# HAL_3.net
KiCad netlist of a schematic drawn in Altium Designer
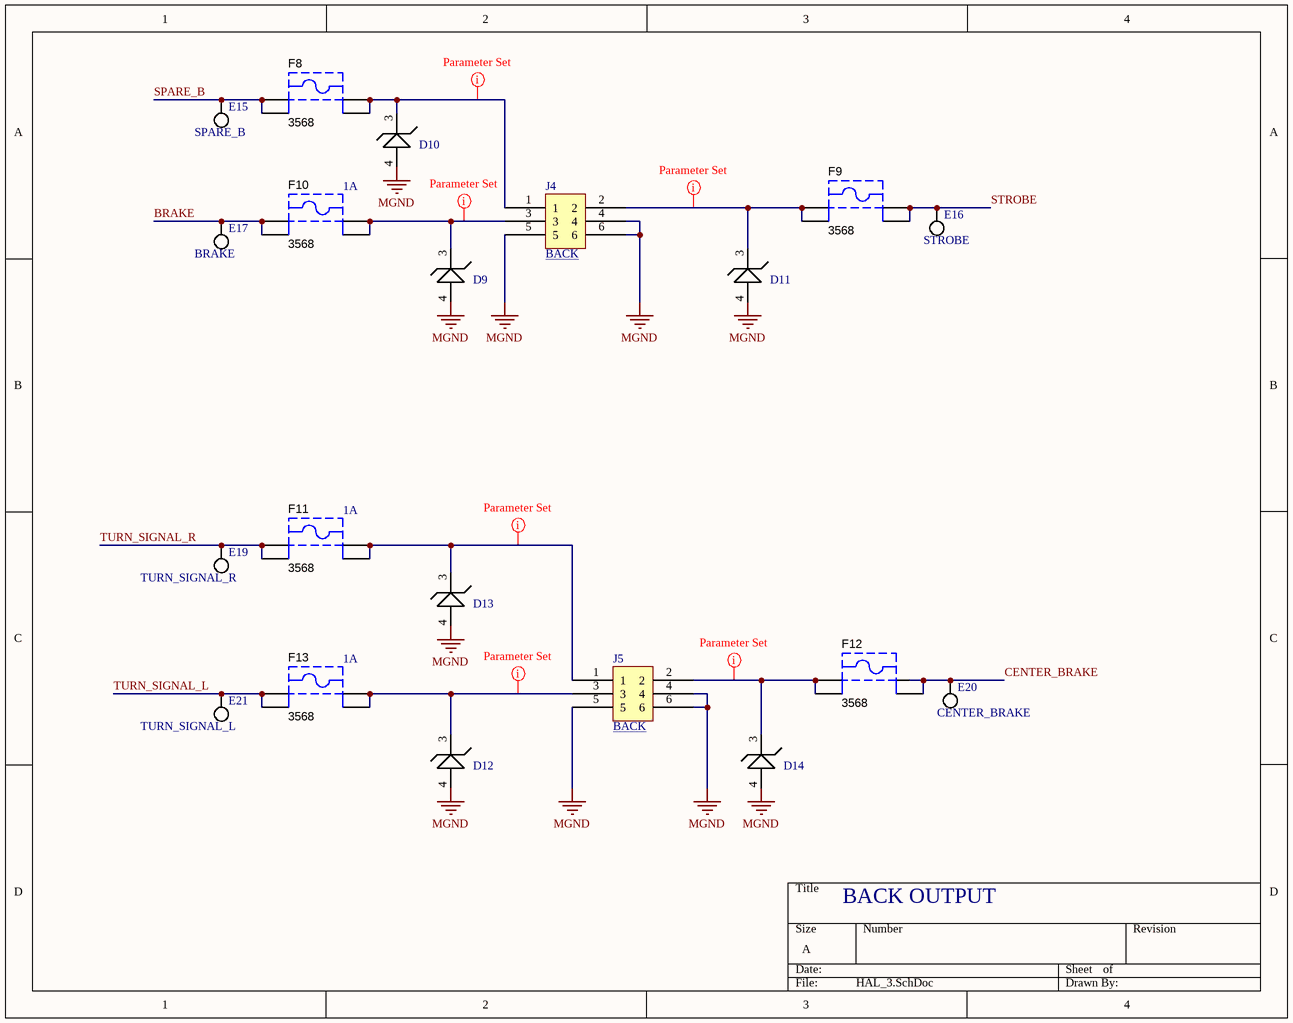
[diagram p0: HAL_3.SchDoc]

(export (version "E")
  (design (tool "Eeschema 10.0.6"))
  (components
    (comp (ref "D9")
      (value "TVS DIODE 12.4V 20.1V DO219AB")
      (footprint "TVS DIODE 12.4V 20.1V DO219AB")
      (libsource (lib "HAL and MotorBoard") (part "TVS DIODE 12.4V 20.1V DO219AB"))
    )
    (comp (ref "D10")
      (value "TVS DIODE 12.4V 20.1V DO219AB")
      (footprint "TVS DIODE 12.4V 20.1V DO219AB")
      (libsource (lib "HAL and MotorBoard") (part "TVS DIODE 12.4V 20.1V DO219AB"))
    )
    (comp (ref "D11")
      (value "TVS DIODE 12.4V 20.1V DO219AB")
      (footprint "TVS DIODE 12.4V 20.1V DO219AB")
      (libsource (lib "HAL and MotorBoard") (part "TVS DIODE 12.4V 20.1V DO219AB"))
    )
    (comp (ref "D12")
      (value "TVS DIODE 12.4V 20.1V DO219AB")
      (footprint "TVS DIODE 12.4V 20.1V DO219AB")
      (libsource (lib "HAL and MotorBoard") (part "TVS DIODE 12.4V 20.1V DO219AB"))
    )
    (comp (ref "D13")
      (value "TVS DIODE 12.4V 20.1V DO219AB")
      (footprint "TVS DIODE 12.4V 20.1V DO219AB")
      (libsource (lib "HAL and MotorBoard") (part "TVS DIODE 12.4V 20.1V DO219AB"))
    )
    (comp (ref "D14")
      (value "TVS DIODE 12.4V 20.1V DO219AB")
      (footprint "TVS DIODE 12.4V 20.1V DO219AB")
      (libsource (lib "HAL and MotorBoard") (part "TVS DIODE 12.4V 20.1V DO219AB"))
    )
    (comp (ref "E15")
      (value "SPARE_B")
      (footprint "EPAD")
      (description "Pad for probing signals")
      (libsource (lib "PrISUm-Discrete") (part "EPAD"))
    )
    (comp (ref "E16")
      (value "STROBE")
      (footprint "EPAD")
      (description "Pad for probing signals")
      (libsource (lib "PrISUm-Discrete") (part "EPAD"))
    )
    (comp (ref "E17")
      (value "BRAKE")
      (footprint "EPAD")
      (description "Pad for probing signals")
      (libsource (lib "PrISUm-Discrete") (part "EPAD"))
    )
    (comp (ref "E19")
      (value "TURN_SIGNAL_R")
      (footprint "EPAD")
      (description "Pad for probing signals")
      (libsource (lib "PrISUm-Discrete") (part "EPAD"))
    )
    (comp (ref "E20")
      (value "CENTER_BRAKE")
      (footprint "EPAD")
      (description "Pad for probing signals")
      (libsource (lib "PrISUm-Discrete") (part "EPAD"))
    )
    (comp (ref "E21")
      (value "TURN_SIGNAL_L")
      (footprint "EPAD")
      (description "Pad for probing signals")
      (libsource (lib "PrISUm-Discrete") (part "EPAD"))
    )
    (comp (ref "F8")
      (value "3568")
      (footprint "KSTN-3568_V")
      (description "Fuse Holder, 20 A, 500 V, -50 to 145 degC, 4-Pin THD, RoHS")
      (fields (field (name "MANUFACTURER") "Keystone"))
      (libsource (lib "Altium Content Vault") (part "FUSE_HOLDER-4"))
    )
    (comp (ref "F9")
      (value "3568")
      (footprint "KSTN-3568_V")
      (description "Fuse Holder, 20 A, 500 V, -50 to 145 degC, 4-Pin THD, RoHS")
      (fields (field (name "MANUFACTURER") "Keystone"))
      (libsource (lib "Altium Content Vault") (part "FUSE_HOLDER-4"))
    )
    (comp (ref "F10")
      (value "3568")
      (footprint "KSTN-3568_V")
      (description "Fuse Holder, 20 A, 500 V, -50 to 145 degC, 4-Pin THD, RoHS")
      (fields (field (name "MANUFACTURER") "Keystone"))
      (libsource (lib "Altium Content Vault") (part "FUSE_HOLDER-4"))
    )
    (comp (ref "F11")
      (value "3568")
      (footprint "KSTN-3568_V")
      (description "Fuse Holder, 20 A, 500 V, -50 to 145 degC, 4-Pin THD, RoHS")
      (fields (field (name "MANUFACTURER") "Keystone"))
      (libsource (lib "Altium Content Vault") (part "FUSE_HOLDER-4"))
    )
    (comp (ref "F12")
      (value "3568")
      (footprint "KSTN-3568_V")
      (description "Fuse Holder, 20 A, 500 V, -50 to 145 degC, 4-Pin THD, RoHS")
      (fields (field (name "MANUFACTURER") "Keystone"))
      (libsource (lib "Altium Content Vault") (part "FUSE_HOLDER-4"))
    )
    (comp (ref "F13")
      (value "3568")
      (footprint "KSTN-3568_V")
      (description "Fuse Holder, 20 A, 500 V, -50 to 145 degC, 4-Pin THD, RoHS")
      (fields (field (name "MANUFACTURER") "Keystone"))
      (libsource (lib "Altium Content Vault") (part "FUSE_HOLDER-4"))
    )
    (comp (ref "J4")
      (value "BACK")
      (footprint "PCBComponent_1 - duplicate")
      (libsource (lib "HAL") (part "6 pin Megafit"))
    )
    (comp (ref "J5")
      (value "BACK")
      (footprint "PCBComponent_1 - duplicate")
      (libsource (lib "HAL") (part "6 pin Megafit"))
    )
  )
  (nets
    (net (code "1") (name "/BRAKE") (class "Default")
      (node (ref "E17") (pin "1") (pinfunction "1_1") (pintype "passive"))
      (node (ref "F10") (pin "1") (pinfunction "1_1") (pintype "passive"))
      (node (ref "F10") (pin "2") (pinfunction "2_2") (pintype "passive"))
    )
    (net (code "2") (name "/CENTER_BRAKE") (class "Default")
      (node (ref "E20") (pin "1") (pinfunction "1_1") (pintype "passive"))
      (node (ref "F12") (pin "3") (pinfunction "3_3") (pintype "passive"))
      (node (ref "F12") (pin "4") (pinfunction "4_4") (pintype "passive"))
    )
    (net (code "3") (name "/SPARE_B") (class "Default")
      (node (ref "E15") (pin "1") (pinfunction "1_1") (pintype "passive"))
      (node (ref "F8") (pin "1") (pinfunction "1_1") (pintype "passive"))
      (node (ref "F8") (pin "2") (pinfunction "2_2") (pintype "passive"))
    )
    (net (code "4") (name "/STROBE") (class "Default")
      (node (ref "E16") (pin "1") (pinfunction "1_1") (pintype "passive"))
      (node (ref "F9") (pin "3") (pinfunction "3_3") (pintype "passive"))
      (node (ref "F9") (pin "4") (pinfunction "4_4") (pintype "passive"))
    )
    (net (code "5") (name "/TURN_SIGNAL_L") (class "Default")
      (node (ref "E21") (pin "1") (pinfunction "1_1") (pintype "passive"))
      (node (ref "F13") (pin "1") (pinfunction "1_1") (pintype "passive"))
      (node (ref "F13") (pin "2") (pinfunction "2_2") (pintype "passive"))
    )
    (net (code "6") (name "/TURN_SIGNAL_R") (class "Default")
      (node (ref "E19") (pin "1") (pinfunction "1_1") (pintype "passive"))
      (node (ref "F11") (pin "1") (pinfunction "1_1") (pintype "passive"))
      (node (ref "F11") (pin "2") (pinfunction "2_2") (pintype "passive"))
    )
    (net (code "7") (name "MGND") (class "Default")
      (node (ref "D10") (pin "4") (pinfunction "4_4") (pintype "passive"))
      (node (ref "D11") (pin "4") (pinfunction "4_4") (pintype "passive"))
      (node (ref "D12") (pin "4") (pinfunction "4_4") (pintype "passive"))
      (node (ref "D13") (pin "4") (pinfunction "4_4") (pintype "passive"))
      (node (ref "D14") (pin "4") (pinfunction "4_4") (pintype "passive"))
      (node (ref "D9") (pin "4") (pinfunction "4_4") (pintype "passive"))
      (node (ref "J4") (pin "4") (pinfunction "4_4") (pintype "passive"))
      (node (ref "J4") (pin "5") (pinfunction "5_5") (pintype "passive"))
      (node (ref "J4") (pin "6") (pinfunction "6_6") (pintype "passive"))
      (node (ref "J5") (pin "4") (pinfunction "4_4") (pintype "passive"))
      (node (ref "J5") (pin "5") (pinfunction "5_5") (pintype "passive"))
      (node (ref "J5") (pin "6") (pinfunction "6_6") (pintype "passive"))
    )
    (net (code "8") (name "Net-(D9-Pad3)") (class "Default")
      (node (ref "D9") (pin "3") (pinfunction "3_3") (pintype "passive"))
      (node (ref "F10") (pin "3") (pinfunction "3_3") (pintype "passive"))
      (node (ref "F10") (pin "4") (pinfunction "4_4") (pintype "passive"))
      (node (ref "J4") (pin "3") (pinfunction "3_3") (pintype "passive"))
    )
    (net (code "9") (name "Net-(D10-Pad3)") (class "Default")
      (node (ref "D10") (pin "3") (pinfunction "3_3") (pintype "passive"))
      (node (ref "F8") (pin "3") (pinfunction "3_3") (pintype "passive"))
      (node (ref "F8") (pin "4") (pinfunction "4_4") (pintype "passive"))
      (node (ref "J4") (pin "1") (pinfunction "1_1") (pintype "passive"))
    )
    (net (code "10") (name "Net-(D11-Pad3)") (class "Default")
      (node (ref "D11") (pin "3") (pinfunction "3_3") (pintype "passive"))
      (node (ref "F9") (pin "1") (pinfunction "1_1") (pintype "passive"))
      (node (ref "F9") (pin "2") (pinfunction "2_2") (pintype "passive"))
      (node (ref "J4") (pin "2") (pinfunction "2_2") (pintype "passive"))
    )
    (net (code "11") (name "Net-(D12-Pad3)") (class "Default")
      (node (ref "D12") (pin "3") (pinfunction "3_3") (pintype "passive"))
      (node (ref "F13") (pin "3") (pinfunction "3_3") (pintype "passive"))
      (node (ref "F13") (pin "4") (pinfunction "4_4") (pintype "passive"))
      (node (ref "J5") (pin "3") (pinfunction "3_3") (pintype "passive"))
    )
    (net (code "12") (name "Net-(D13-Pad3)") (class "Default")
      (node (ref "D13") (pin "3") (pinfunction "3_3") (pintype "passive"))
      (node (ref "F11") (pin "3") (pinfunction "3_3") (pintype "passive"))
      (node (ref "F11") (pin "4") (pinfunction "4_4") (pintype "passive"))
      (node (ref "J5") (pin "1") (pinfunction "1_1") (pintype "passive"))
    )
    (net (code "13") (name "Net-(D14-Pad3)") (class "Default")
      (node (ref "D14") (pin "3") (pinfunction "3_3") (pintype "passive"))
      (node (ref "F12") (pin "1") (pinfunction "1_1") (pintype "passive"))
      (node (ref "F12") (pin "2") (pinfunction "2_2") (pintype "passive"))
      (node (ref "J5") (pin "2") (pinfunction "2_2") (pintype "passive"))
    )
  )
)
